# ESP32.net
KiCad netlist of a schematic drawn in Altium Designer
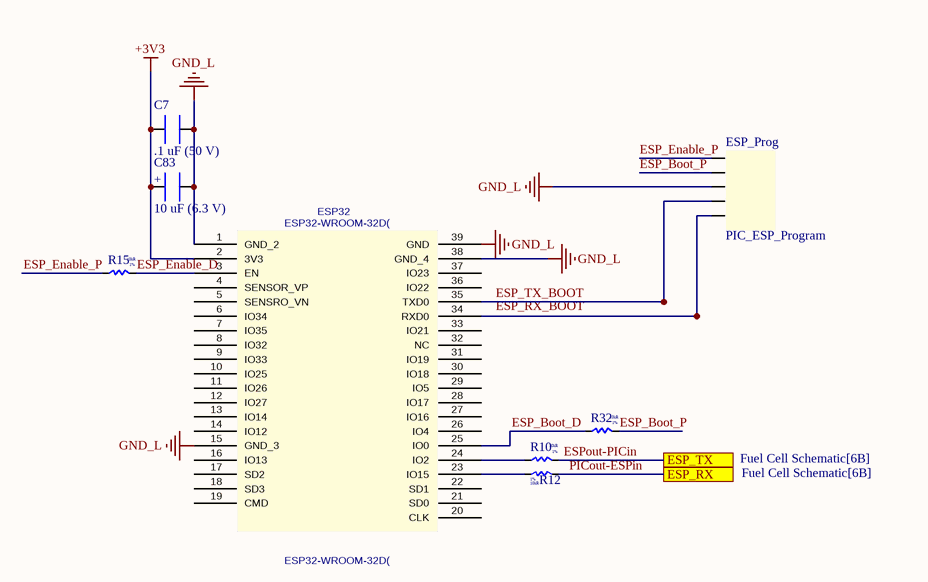
[diagram p0: ESP32.SchDoc]

(export (version "E")
  (design (tool "Eeschema 10.0.6"))
  (components
    (comp (ref "C7")
      (value ".1 uF (50 V)")
      (footprint ".1uF capacitor")
      (libsource (lib "Schlib1") (part ".1 uF cap"))
    )
    (comp (ref "C83")
      (value "10 uF (6.3 V)")
      (footprint "10 uF cap")
      (libsource (lib "Schlib1") (part "10 uF cap"))
    )
    (comp (ref "ESP32")
      (value "ESP32-WROOM-32D(")
      (footprint "ESP32")
      (fields
        (field (name "MANUFACTURER_PART_NUMBER") "ESP32-WROOM-32D(M113DH6400PH3Q0)")
        (field (name "ALTIUM_VALUE") "ESP32-WROOM-32D(")
        (field (name "COPYRIGHT") "Copyright (C) 2023 Ultra Librarian. All rights reserved.")
      )
      (libsource (lib "Schlib1") (part "ESP32-WROOM-32D("))
    )
    (comp (ref "ESP_Prog")
      (value "PIC_ESP_Program")
      (footprint "ESP_Program")
      (libsource (lib "Schlib1") (part "PIC_ESP_Program"))
    )
    (comp (ref "R10")
      (value "~")
      (footprint "Resistor_YAGEO_0805")
      (description "RES 10K OHM 1% 1/8W 0805")
      (fields
        (field (name "MANUFACTURER") "Yageo")
        (field (name "MANUFACTURER PART NUMBER") "RC0805FR-1010KL")
        (field (name "TOLERANCE") "1%")
        (field (name "RESISTANCE") "10kR")
      )
      (libsource (lib "Schlib1") (part "RC0805FR-1010KL"))
    )
    (comp (ref "R12")
      (value "~")
      (footprint "Resistor_YAGEO_0805")
      (description "RES 10K OHM 1% 1/8W 0805")
      (fields
        (field (name "MANUFACTURER") "Yageo")
        (field (name "MANUFACTURER PART NUMBER") "RC0805FR-1010KL")
        (field (name "TOLERANCE") "1%")
        (field (name "RESISTANCE") "10kR")
      )
      (libsource (lib "Schlib1") (part "RC0805FR-1010KL"))
    )
    (comp (ref "R15")
      (value "~")
      (footprint "Resistor_YAGEO_0805")
      (description "RES 10K OHM 1% 1/8W 0805")
      (fields
        (field (name "MANUFACTURER") "Yageo")
        (field (name "MANUFACTURER PART NUMBER") "RC0805FR-1010KL")
        (field (name "TOLERANCE") "1%")
        (field (name "RESISTANCE") "10kR")
      )
      (libsource (lib "Schlib1") (part "RC0805FR-1010KL"))
    )
    (comp (ref "R32")
      (value "~")
      (footprint "Resistor_YAGEO_0805")
      (description "RES 10K OHM 1% 1/8W 0805")
      (fields
        (field (name "MANUFACTURER") "Yageo")
        (field (name "MANUFACTURER PART NUMBER") "RC0805FR-1010KL")
        (field (name "TOLERANCE") "1%")
        (field (name "RESISTANCE") "10kR")
      )
      (libsource (lib "Schlib1") (part "RC0805FR-1010KL"))
    )
  )
  (nets
    (net (code "1") (name "+3V3") (class "Default")
      (node (ref "C7") (pin "1") (pinfunction "1_1") (pintype "passive"))
      (node (ref "C83") (pin "1") (pinfunction "1_1") (pintype "passive"))
      (node (ref "ESP32") (pin "2") (pinfunction "3V3_2") (pintype "passive"))
    )
    (net (code "2") (name "/ESP_Boot_D") (class "Default")
      (node (ref "ESP32") (pin "25") (pinfunction "IO0_25") (pintype "passive"))
      (node (ref "R32") (pin "1") (pinfunction "1_1") (pintype "passive"))
    )
    (net (code "3") (name "/ESP_Boot_P") (class "Default")
      (node (ref "ESP_Prog") (pin "4") (pinfunction "Boot_4") (pintype "passive"))
      (node (ref "R32") (pin "2") (pinfunction "2_2") (pintype "passive"))
    )
    (net (code "4") (name "/ESP_Enable_D") (class "Default")
      (node (ref "ESP32") (pin "3") (pinfunction "EN_3") (pintype "passive"))
      (node (ref "R15") (pin "2") (pinfunction "2_2") (pintype "passive"))
    )
    (net (code "5") (name "/ESP_Enable_P") (class "Default")
      (node (ref "ESP_Prog") (pin "5") (pinfunction "Enable_5") (pintype "passive"))
      (node (ref "R15") (pin "1") (pinfunction "1_1") (pintype "passive"))
    )
    (net (code "7") (name "/ESP_TX_BOOT") (class "Default")
      (node (ref "ESP32") (pin "35") (pinfunction "TXD0_35") (pintype "passive"))
      (node (ref "ESP_Prog") (pin "2") (pinfunction "RX_2") (pintype "passive"))
    )
    (net (code "8") (name "/ESPout-PICin") (class "Default")
      (node (ref "R10") (pin "2") (pinfunction "2_2") (pintype "passive"))
    )
    (net (code "9") (name "/PICout-ESPin") (class "Default")
      (node (ref "R12") (pin "2") (pinfunction "2_2") (pintype "passive"))
    )
    (net (code "10") (name "GND_L") (class "Default")
      (node (ref "C7") (pin "2") (pinfunction "2_2") (pintype "passive"))
      (node (ref "C83") (pin "2") (pinfunction "2_2") (pintype "passive"))
      (node (ref "ESP32") (pin "1") (pinfunction "GND_2_1") (pintype "passive"))
      (node (ref "ESP32") (pin "15") (pinfunction "GND_3_15") (pintype "passive"))
      (node (ref "ESP32") (pin "38") (pinfunction "GND_4_38") (pintype "passive"))
      (node (ref "ESP32") (pin "39") (pinfunction "GND_39") (pintype "passive"))
      (node (ref "ESP_Prog") (pin "3") (pinfunction "GND_3") (pintype "passive"))
    )
    (net (code "11") (name "Net-(ESP32-IO2)") (class "Default")
      (node (ref "ESP32") (pin "24") (pinfunction "IO2_24") (pintype "passive"))
      (node (ref "R10") (pin "1") (pinfunction "1_1") (pintype "passive"))
    )
    (net (code "12") (name "Net-(ESP32-IO15)") (class "Default")
      (node (ref "ESP32") (pin "23") (pinfunction "IO15_23") (pintype "passive"))
      (node (ref "R12") (pin "1") (pinfunction "1_1") (pintype "passive"))
    )
    (net (code "13") (name "Net-(ESP32-RXD0)") (class "Default")
      (node (ref "ESP32") (pin "34") (pinfunction "RXD0_34") (pintype "passive"))
      (node (ref "ESP_Prog") (pin "1") (pinfunction "TX_1") (pintype "passive"))
    )
    (net (code "14") (name "unconnected-(ESP32-CLK-Pad20)") (class "Default")
      (node (ref "ESP32") (pin "20") (pinfunction "CLK_20") (pintype "passive"))
    )
    (net (code "15") (name "unconnected-(ESP32-CMD-Pad19)") (class "Default")
      (node (ref "ESP32") (pin "19") (pinfunction "CMD_19") (pintype "passive"))
    )
    (net (code "16") (name "unconnected-(ESP32-IO4-Pad26)") (class "Default")
      (node (ref "ESP32") (pin "26") (pinfunction "IO4_26") (pintype "passive"))
    )
    (net (code "17") (name "unconnected-(ESP32-IO5-Pad29)") (class "Default")
      (node (ref "ESP32") (pin "29") (pinfunction "IO5_29") (pintype "passive"))
    )
    (net (code "18") (name "unconnected-(ESP32-IO12-Pad14)") (class "Default")
      (node (ref "ESP32") (pin "14") (pinfunction "IO12_14") (pintype "passive"))
    )
    (net (code "19") (name "unconnected-(ESP32-IO13-Pad16)") (class "Default")
      (node (ref "ESP32") (pin "16") (pinfunction "IO13_16") (pintype "passive"))
    )
    (net (code "20") (name "unconnected-(ESP32-IO14-Pad13)") (class "Default")
      (node (ref "ESP32") (pin "13") (pinfunction "IO14_13") (pintype "passive"))
    )
    (net (code "21") (name "unconnected-(ESP32-IO16-Pad27)") (class "Default")
      (node (ref "ESP32") (pin "27") (pinfunction "IO16_27") (pintype "passive"))
    )
    (net (code "22") (name "unconnected-(ESP32-IO17-Pad28)") (class "Default")
      (node (ref "ESP32") (pin "28") (pinfunction "IO17_28") (pintype "passive"))
    )
    (net (code "23") (name "unconnected-(ESP32-IO18-Pad30)") (class "Default")
      (node (ref "ESP32") (pin "30") (pinfunction "IO18_30") (pintype "passive"))
    )
    (net (code "24") (name "unconnected-(ESP32-IO19-Pad31)") (class "Default")
      (node (ref "ESP32") (pin "31") (pinfunction "IO19_31") (pintype "passive"))
    )
    (net (code "25") (name "unconnected-(ESP32-IO21-Pad33)") (class "Default")
      (node (ref "ESP32") (pin "33") (pinfunction "IO21_33") (pintype "passive"))
    )
    (net (code "26") (name "unconnected-(ESP32-IO22-Pad36)") (class "Default")
      (node (ref "ESP32") (pin "36") (pinfunction "IO22_36") (pintype "passive"))
    )
    (net (code "27") (name "unconnected-(ESP32-IO23-Pad37)") (class "Default")
      (node (ref "ESP32") (pin "37") (pinfunction "IO23_37") (pintype "passive"))
    )
    (net (code "28") (name "unconnected-(ESP32-IO25-Pad10)") (class "Default")
      (node (ref "ESP32") (pin "10") (pinfunction "IO25_10") (pintype "passive"))
    )
    (net (code "29") (name "unconnected-(ESP32-IO26-Pad11)") (class "Default")
      (node (ref "ESP32") (pin "11") (pinfunction "IO26_11") (pintype "passive"))
    )
    (net (code "30") (name "unconnected-(ESP32-IO27-Pad12)") (class "Default")
      (node (ref "ESP32") (pin "12") (pinfunction "IO27_12") (pintype "passive"))
    )
    (net (code "31") (name "unconnected-(ESP32-IO32-Pad8)") (class "Default")
      (node (ref "ESP32") (pin "8") (pinfunction "IO32_8") (pintype "passive"))
    )
    (net (code "32") (name "unconnected-(ESP32-IO33-Pad9)") (class "Default")
      (node (ref "ESP32") (pin "9") (pinfunction "IO33_9") (pintype "passive"))
    )
    (net (code "33") (name "unconnected-(ESP32-IO34-Pad6)") (class "Default")
      (node (ref "ESP32") (pin "6") (pinfunction "IO34_6") (pintype "passive"))
    )
    (net (code "34") (name "unconnected-(ESP32-IO35-Pad7)") (class "Default")
      (node (ref "ESP32") (pin "7") (pinfunction "IO35_7") (pintype "passive"))
    )
    (net (code "35") (name "unconnected-(ESP32-NC-Pad32)") (class "Default")
      (node (ref "ESP32") (pin "32") (pinfunction "NC_32") (pintype "passive"))
    )
    (net (code "36") (name "unconnected-(ESP32-SD0-Pad21)") (class "Default")
      (node (ref "ESP32") (pin "21") (pinfunction "SD0_21") (pintype "passive"))
    )
    (net (code "37") (name "unconnected-(ESP32-SD1-Pad22)") (class "Default")
      (node (ref "ESP32") (pin "22") (pinfunction "SD1_22") (pintype "passive"))
    )
    (net (code "38") (name "unconnected-(ESP32-SD2-Pad17)") (class "Default")
      (node (ref "ESP32") (pin "17") (pinfunction "SD2_17") (pintype "passive"))
    )
    (net (code "39") (name "unconnected-(ESP32-SD3-Pad18)") (class "Default")
      (node (ref "ESP32") (pin "18") (pinfunction "SD3_18") (pintype "passive"))
    )
    (net (code "40") (name "unconnected-(ESP32-SENSOR_VP-Pad4)") (class "Default")
      (node (ref "ESP32") (pin "4") (pinfunction "SENSOR_VP_4") (pintype "passive"))
    )
    (net (code "41") (name "unconnected-(ESP32-SENSRO_VN-Pad5)") (class "Default")
      (node (ref "ESP32") (pin "5") (pinfunction "SENSRO_VN_5") (pintype "passive"))
    )
  )
)
